# 12V_-_3V3_Buck_1_5A_discrete.net
KiCad netlist of a schematic drawn in EAGLE
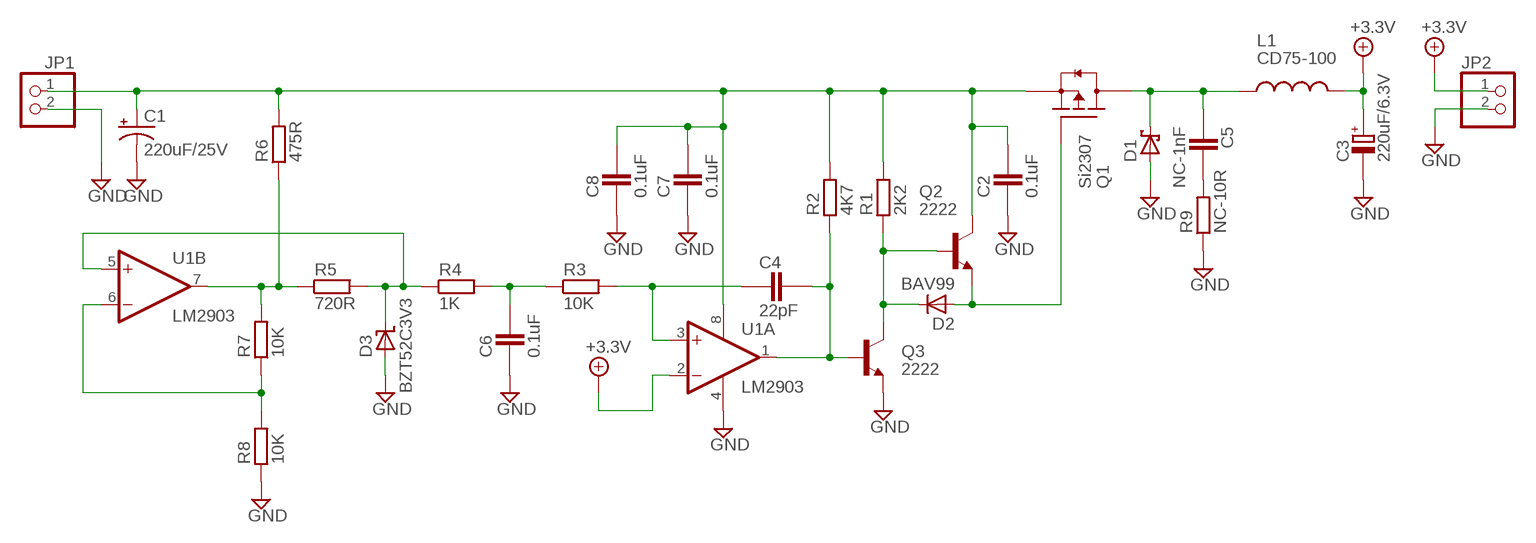
[diagram p0: schematic, sheet 1]

(export (version "E")
  (design (tool "Eeschema 10.0.6"))
  (components
    (comp (ref "C1")
      (value "220uF/25V")
      (footprint "eagle-import:PANASONIC_G")
      (libsource (lib "eagle-import") (part "CAP_POLG"))
    )
    (comp (ref "C2")
      (value "0.1uF")
      (footprint "eagle-import:CAPC2012X145AN")
      (libsource (lib "eagle-import") (part "CAPACITOR_0805"))
    )
    (comp (ref "C3")
      (value "220uF/6.3V")
      (footprint "eagle-import:CAPMP7343X310N")
      (libsource (lib "eagle-import") (part "POLARISED_D_CASE"))
    )
    (comp (ref "C4")
      (value "22pF")
      (footprint "eagle-import:CAPC1608X92N")
      (libsource (lib "eagle-import") (part "CAPACITOR_0603"))
    )
    (comp (ref "C5")
      (value "NC-1nF")
      (footprint "eagle-import:CAPC1608X92N")
      (libsource (lib "eagle-import") (part "CAPACITOR_0603"))
    )
    (comp (ref "C6")
      (value "0.1uF")
      (footprint "eagle-import:CAPC1608X92N")
      (libsource (lib "eagle-import") (part "CAPACITOR_0603"))
    )
    (comp (ref "C7")
      (value "0.1uF")
      (footprint "eagle-import:CAPC1608X92N")
      (libsource (lib "eagle-import") (part "CAPACITOR_0603"))
    )
    (comp (ref "C8")
      (value "0.1uF")
      (footprint "eagle-import:CAPC1608X92N")
      (libsource (lib "eagle-import") (part "CAPACITOR_0603"))
    )
    (comp (ref "D1")
      (value "SCHOTTKY_SMC")
      (footprint "eagle-import:DIOM7959X265N")
      (libsource (lib "eagle-import") (part "SCHOTTKY_SMC"))
    )
    (comp (ref "D2")
      (value "BAV99")
      (footprint "eagle-import:SOT95P280X135-3N")
      (libsource (lib "eagle-import") (part "DIODE_SOT-23"))
    )
    (comp (ref "D3")
      (value "BZT52C3V3")
      (footprint "eagle-import:SOD2514X100N")
      (libsource (lib "eagle-import") (part "ZENER_SOD-323"))
    )
    (comp (ref "JP1")
      (value "PINHD-1X2_2.54")
      (footprint "eagle-import:1X02")
      (libsource (lib "eagle-import") (part "PINHD-1X2_2.54"))
    )
    (comp (ref "JP2")
      (value "PINHD-1X2_2.54")
      (footprint "eagle-import:1X02")
      (libsource (lib "eagle-import") (part "PINHD-1X2_2.54"))
    )
    (comp (ref "L1")
      (value "CD75-100")
      (footprint "eagle-import:CD75")
      (libsource (lib "eagle-import") (part "CD75"))
    )
    (comp (ref "Q1")
      (value "Si2307")
      (footprint "eagle-import:SOT95P280X135-3N")
      (libsource (lib "eagle-import") (part "MOSFET-PCH_SOT-23"))
    )
    (comp (ref "Q2")
      (value "2222")
      (footprint "eagle-import:SOT95P280X135-3N")
      (libsource (lib "eagle-import") (part "NPN_SOT-23"))
    )
    (comp (ref "Q3")
      (value "2222")
      (footprint "eagle-import:SOT95P280X135-3N")
      (libsource (lib "eagle-import") (part "NPN_SOT-23"))
    )
    (comp (ref "R1")
      (value "2K2")
      (footprint "eagle-import:RESC1608X55N")
      (libsource (lib "eagle-import") (part "RESISTOR_0603"))
    )
    (comp (ref "R2")
      (value "4K7")
      (footprint "eagle-import:RESC1608X55N")
      (libsource (lib "eagle-import") (part "RESISTOR_0603"))
    )
    (comp (ref "R3")
      (value "10K")
      (footprint "eagle-import:RESC3115X70N")
      (libsource (lib "eagle-import") (part "RESISTOR_1206"))
    )
    (comp (ref "R4")
      (value "1K")
      (footprint "eagle-import:RESC1608X55N")
      (libsource (lib "eagle-import") (part "RESISTOR_0603"))
    )
    (comp (ref "R5")
      (value "720R")
      (footprint "eagle-import:RESC1608X55N")
      (libsource (lib "eagle-import") (part "RESISTOR_0603"))
    )
    (comp (ref "R6")
      (value "475R")
      (footprint "eagle-import:RESC1608X55N")
      (libsource (lib "eagle-import") (part "RESISTOR_0603"))
    )
    (comp (ref "R7")
      (value "10K")
      (footprint "eagle-import:RESC1608X55N")
      (libsource (lib "eagle-import") (part "RESISTOR_0603"))
    )
    (comp (ref "R8")
      (value "10K")
      (footprint "eagle-import:RESC1608X55N")
      (libsource (lib "eagle-import") (part "RESISTOR_0603"))
    )
    (comp (ref "R9")
      (value "NC-10R")
      (footprint "eagle-import:RESC1608X55N")
      (libsource (lib "eagle-import") (part "RESISTOR_0603"))
    )
    (comp (ref "U1")
      (value "LM2903")
      (footprint "eagle-import:SO08")
      (libsource (lib "eagle-import") (part "LM393D"))
    )
  )
  (nets
    (net (code "1") (name "+3.3V") (class "Default")
      (node (ref "C3") (pin "+") (pinfunction "+_+") (pintype "passive"))
      (node (ref "JP2") (pin "1") (pinfunction "1_1") (pintype "passive"))
      (node (ref "L1") (pin "2") (pinfunction "2_2") (pintype "passive"))
      (node (ref "U1") (pin "2") (pinfunction "-IN_2") (pintype "input"))
    )
    (net (code "2") (name "GND") (class "Default")
      (node (ref "C1") (pin "-") (pinfunction "-_-") (pintype "passive"))
      (node (ref "C2") (pin "1") (pinfunction "1_1") (pintype "passive"))
      (node (ref "C3") (pin "-") (pinfunction "-_-") (pintype "passive"))
      (node (ref "C6") (pin "1") (pinfunction "1_1") (pintype "passive"))
      (node (ref "C7") (pin "1") (pinfunction "1_1") (pintype "passive"))
      (node (ref "C8") (pin "1") (pinfunction "1_1") (pintype "passive"))
      (node (ref "D1") (pin "A") (pinfunction "A_A") (pintype "passive"))
      (node (ref "D3") (pin "A") (pinfunction "A_A") (pintype "passive"))
      (node (ref "JP1") (pin "2") (pinfunction "2_2") (pintype "passive"))
      (node (ref "JP2") (pin "2") (pinfunction "2_2") (pintype "passive"))
      (node (ref "Q3") (pin "2") (pinfunction "E_2") (pintype "passive"))
      (node (ref "R8") (pin "1") (pinfunction "1_1") (pintype "passive"))
      (node (ref "R9") (pin "1") (pinfunction "1_1") (pintype "passive"))
      (node (ref "U1") (pin "4") (pinfunction "V-_4") (pintype "power_in"))
    )
    (net (code "3") (name "Net-(C5-Pad2)") (class "Default")
      (node (ref "C5") (pin "2") (pinfunction "2_2") (pintype "passive"))
      (node (ref "R9") (pin "2") (pinfunction "2_2") (pintype "passive"))
    )
    (net (code "4") (name "Net-(C6-Pad2)") (class "Default")
      (node (ref "C6") (pin "2") (pinfunction "2_2") (pintype "passive"))
      (node (ref "R3") (pin "1") (pinfunction "1_1") (pintype "passive"))
      (node (ref "R4") (pin "2") (pinfunction "2_2") (pintype "passive"))
    )
    (net (code "5") (name "Net-(D2-A)") (class "Default")
      (node (ref "D2") (pin "1") (pinfunction "A_1") (pintype "passive"))
      (node (ref "Q1") (pin "1") (pinfunction "G_1") (pintype "passive"))
      (node (ref "Q2") (pin "2") (pinfunction "E_2") (pintype "passive"))
    )
    (net (code "6") (name "Net-(D2-K)") (class "Default")
      (node (ref "D2") (pin "3") (pinfunction "K_3") (pintype "passive"))
      (node (ref "Q2") (pin "1") (pinfunction "B_1") (pintype "passive"))
      (node (ref "Q3") (pin "3") (pinfunction "C_3") (pintype "passive"))
      (node (ref "R1") (pin "1") (pinfunction "1_1") (pintype "passive"))
    )
    (net (code "7") (name "Net-(Q1-D)") (class "Default")
      (node (ref "C5") (pin "1") (pinfunction "1_1") (pintype "passive"))
      (node (ref "D1") (pin "K") (pinfunction "K_K") (pintype "passive"))
      (node (ref "L1") (pin "1") (pinfunction "1_1") (pintype "passive"))
      (node (ref "Q1") (pin "3") (pinfunction "D_3") (pintype "passive"))
    )
    (net (code "8") (name "Net-(Q1-S)") (class "Default")
      (node (ref "C1") (pin "+") (pinfunction "+_+") (pintype "passive"))
      (node (ref "C2") (pin "2") (pinfunction "2_2") (pintype "passive"))
      (node (ref "C7") (pin "2") (pinfunction "2_2") (pintype "passive"))
      (node (ref "C8") (pin "2") (pinfunction "2_2") (pintype "passive"))
      (node (ref "JP1") (pin "1") (pinfunction "1_1") (pintype "passive"))
      (node (ref "Q1") (pin "2") (pinfunction "S_2") (pintype "passive"))
      (node (ref "Q2") (pin "3") (pinfunction "C_3") (pintype "passive"))
      (node (ref "R1") (pin "2") (pinfunction "2_2") (pintype "passive"))
      (node (ref "R2") (pin "2") (pinfunction "2_2") (pintype "passive"))
      (node (ref "R6") (pin "2") (pinfunction "2_2") (pintype "passive"))
      (node (ref "U1") (pin "8") (pinfunction "V+_8") (pintype "power_in"))
    )
    (net (code "9") (name "Net-(Q3-B)") (class "Default")
      (node (ref "C4") (pin "2") (pinfunction "2_2") (pintype "passive"))
      (node (ref "Q3") (pin "1") (pinfunction "B_1") (pintype "passive"))
      (node (ref "R2") (pin "1") (pinfunction "1_1") (pintype "passive"))
      (node (ref "U1") (pin "1") (pinfunction "OUT_1") (pintype "output"))
    )
    (net (code "10") (name "Net-(U1A-+IN)") (class "Default")
      (node (ref "C4") (pin "1") (pinfunction "1_1") (pintype "passive"))
      (node (ref "R3") (pin "2") (pinfunction "2_2") (pintype "passive"))
      (node (ref "U1") (pin "3") (pinfunction "+IN_3") (pintype "input"))
    )
    (net (code "11") (name "Net-(U1B-+IN)") (class "Default")
      (node (ref "D3") (pin "K") (pinfunction "K_K") (pintype "passive"))
      (node (ref "R4") (pin "1") (pinfunction "1_1") (pintype "passive"))
      (node (ref "R5") (pin "2") (pinfunction "2_2") (pintype "passive"))
      (node (ref "U1") (pin "5") (pinfunction "+IN_5") (pintype "input"))
    )
    (net (code "12") (name "Net-(U1B--IN)") (class "Default")
      (node (ref "R7") (pin "1") (pinfunction "1_1") (pintype "passive"))
      (node (ref "R8") (pin "2") (pinfunction "2_2") (pintype "passive"))
      (node (ref "U1") (pin "6") (pinfunction "-IN_6") (pintype "input"))
    )
    (net (code "13") (name "Net-(U1B-OUT)") (class "Default")
      (node (ref "R5") (pin "1") (pinfunction "1_1") (pintype "passive"))
      (node (ref "R6") (pin "1") (pinfunction "1_1") (pintype "passive"))
      (node (ref "R7") (pin "2") (pinfunction "2_2") (pintype "passive"))
      (node (ref "U1") (pin "7") (pinfunction "OUT_7") (pintype "output"))
    )
  )
)
